# GYRO.net
KiCad netlist of a schematic drawn in EAGLE
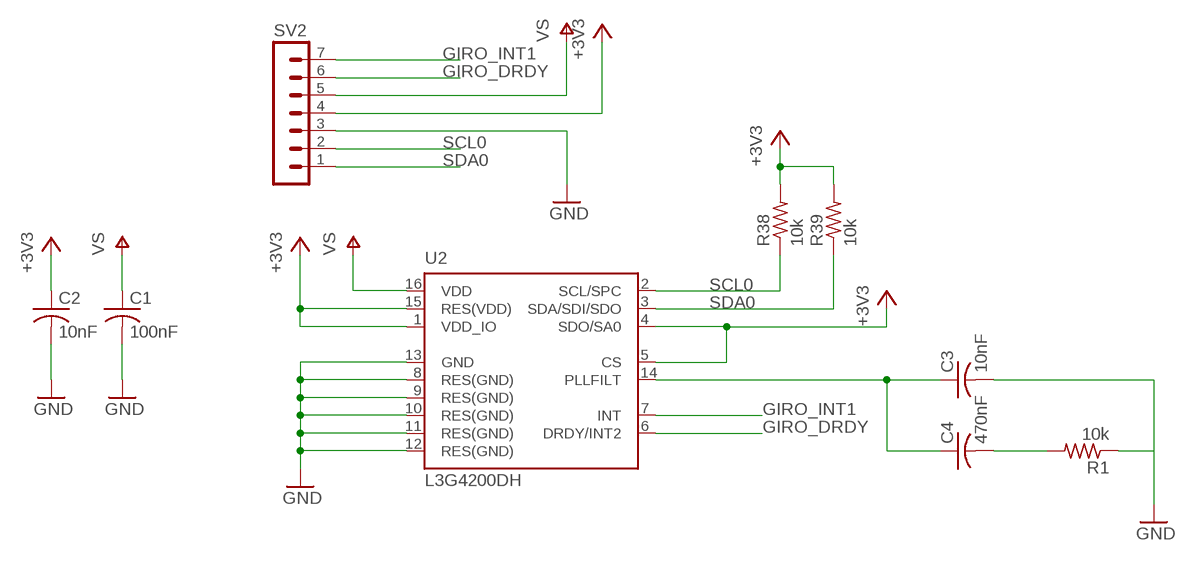
[diagram p0: schematic, sheet 1]

(export (version "E")
  (design (tool "Eeschema 10.0.6"))
  (components
    (comp (ref "C1")
      (value "100nF")
      (footprint "eagle-import:C0805")
      (libsource (lib "eagle-import") (part "C-USC0805"))
    )
    (comp (ref "C2")
      (value "10nF")
      (footprint "eagle-import:C0805")
      (libsource (lib "eagle-import") (part "C-USC0805"))
    )
    (comp (ref "C3")
      (value "10nF")
      (footprint "eagle-import:C0805")
      (libsource (lib "eagle-import") (part "C-USC0805"))
    )
    (comp (ref "C4")
      (value "470nF")
      (footprint "eagle-import:C0805")
      (libsource (lib "eagle-import") (part "C-USC0805"))
    )
    (comp (ref "R1")
      (value "10k")
      (footprint "eagle-import:R0805")
      (libsource (lib "eagle-import") (part "R-US_R0805"))
    )
    (comp (ref "R38")
      (value "10k")
      (footprint "eagle-import:R0805")
      (libsource (lib "eagle-import") (part "R-US_R0805"))
    )
    (comp (ref "R39")
      (value "10k")
      (footprint "eagle-import:R0805")
      (libsource (lib "eagle-import") (part "R-US_R0805"))
    )
    (comp (ref "SV2")
      (value "MA07-1")
      (footprint "eagle-import:MA07-1")
      (libsource (lib "eagle-import") (part "MA07-1"))
    )
    (comp (ref "U2")
      (value "L3G4200DH")
      (footprint "eagle-import:LGA-16L")
      (libsource (lib "eagle-import") (part "L3G4200DH"))
    )
  )
  (nets
    (net (code "1") (name "+3V3") (class "Default")
      (node (ref "C2") (pin "1") (pinfunction "1_1") (pintype "passive"))
      (node (ref "R38") (pin "2") (pinfunction "2_2") (pintype "passive"))
      (node (ref "R39") (pin "2") (pinfunction "2_2") (pintype "passive"))
      (node (ref "SV2") (pin "4") (pinfunction "4_4") (pintype "passive"))
      (node (ref "U2") (pin "1") (pinfunction "VDD_IO_1") (pintype "power_in"))
      (node (ref "U2") (pin "15") (pinfunction "RES(VDD)_15") (pintype "power_in"))
      (node (ref "U2") (pin "4") (pinfunction "SDO/SA0_4") (pintype "output"))
      (node (ref "U2") (pin "5") (pinfunction "CS_5") (pintype "input"))
    )
    (net (code "2") (name "/GIRO_DRDY") (class "Default")
      (node (ref "SV2") (pin "6") (pinfunction "6_6") (pintype "passive"))
      (node (ref "U2") (pin "6") (pinfunction "DRDY/INT2_6") (pintype "bidirectional"))
    )
    (net (code "3") (name "/GIRO_INT1") (class "Default")
      (node (ref "SV2") (pin "7") (pinfunction "7_7") (pintype "passive"))
      (node (ref "U2") (pin "7") (pinfunction "INT_7") (pintype "output"))
    )
    (net (code "4") (name "/SCL0") (class "Default")
      (node (ref "R38") (pin "1") (pinfunction "1_1") (pintype "passive"))
      (node (ref "SV2") (pin "2") (pinfunction "2_2") (pintype "passive"))
      (node (ref "U2") (pin "2") (pinfunction "SCL/SPC_2") (pintype "input"))
    )
    (net (code "5") (name "/SDA0") (class "Default")
      (node (ref "R39") (pin "1") (pinfunction "1_1") (pintype "passive"))
      (node (ref "SV2") (pin "1") (pinfunction "1_1") (pintype "passive"))
      (node (ref "U2") (pin "3") (pinfunction "SDA/SDI/SDO_3") (pintype "bidirectional"))
    )
    (net (code "6") (name "GND") (class "Default")
      (node (ref "C1") (pin "2") (pinfunction "2_2") (pintype "passive"))
      (node (ref "C2") (pin "2") (pinfunction "2_2") (pintype "passive"))
      (node (ref "C3") (pin "2") (pinfunction "2_2") (pintype "passive"))
      (node (ref "R1") (pin "1") (pinfunction "1_1") (pintype "passive"))
      (node (ref "SV2") (pin "3") (pinfunction "3_3") (pintype "passive"))
      (node (ref "U2") (pin "10") (pinfunction "RES(GND)_10") (pintype "power_in"))
      (node (ref "U2") (pin "11") (pinfunction "RES(GND)_11") (pintype "power_in"))
      (node (ref "U2") (pin "12") (pinfunction "RES(GND)_12") (pintype "power_in"))
      (node (ref "U2") (pin "13") (pinfunction "GND_13") (pintype "power_in"))
      (node (ref "U2") (pin "8") (pinfunction "RES(GND)_8") (pintype "power_in"))
      (node (ref "U2") (pin "9") (pinfunction "RES(GND)_9") (pintype "power_in"))
    )
    (net (code "7") (name "Net-(C4-Pad2)") (class "Default")
      (node (ref "C4") (pin "2") (pinfunction "2_2") (pintype "passive"))
      (node (ref "R1") (pin "2") (pinfunction "2_2") (pintype "passive"))
    )
    (net (code "8") (name "Net-(U2-PLLFILT)") (class "Default")
      (node (ref "C3") (pin "1") (pinfunction "1_1") (pintype "passive"))
      (node (ref "C4") (pin "1") (pinfunction "1_1") (pintype "passive"))
      (node (ref "U2") (pin "14") (pinfunction "PLLFILT_14") (pintype "output"))
    )
    (net (code "9") (name "VS") (class "Default")
      (node (ref "C1") (pin "1") (pinfunction "1_1") (pintype "passive"))
      (node (ref "SV2") (pin "5") (pinfunction "5_5") (pintype "passive"))
      (node (ref "U2") (pin "16") (pinfunction "VDD_16") (pintype "power_in"))
    )
  )
)
